# intellectual_roaddeng.net
KiCad netlist of a schematic drawn in EasyEDA Pro
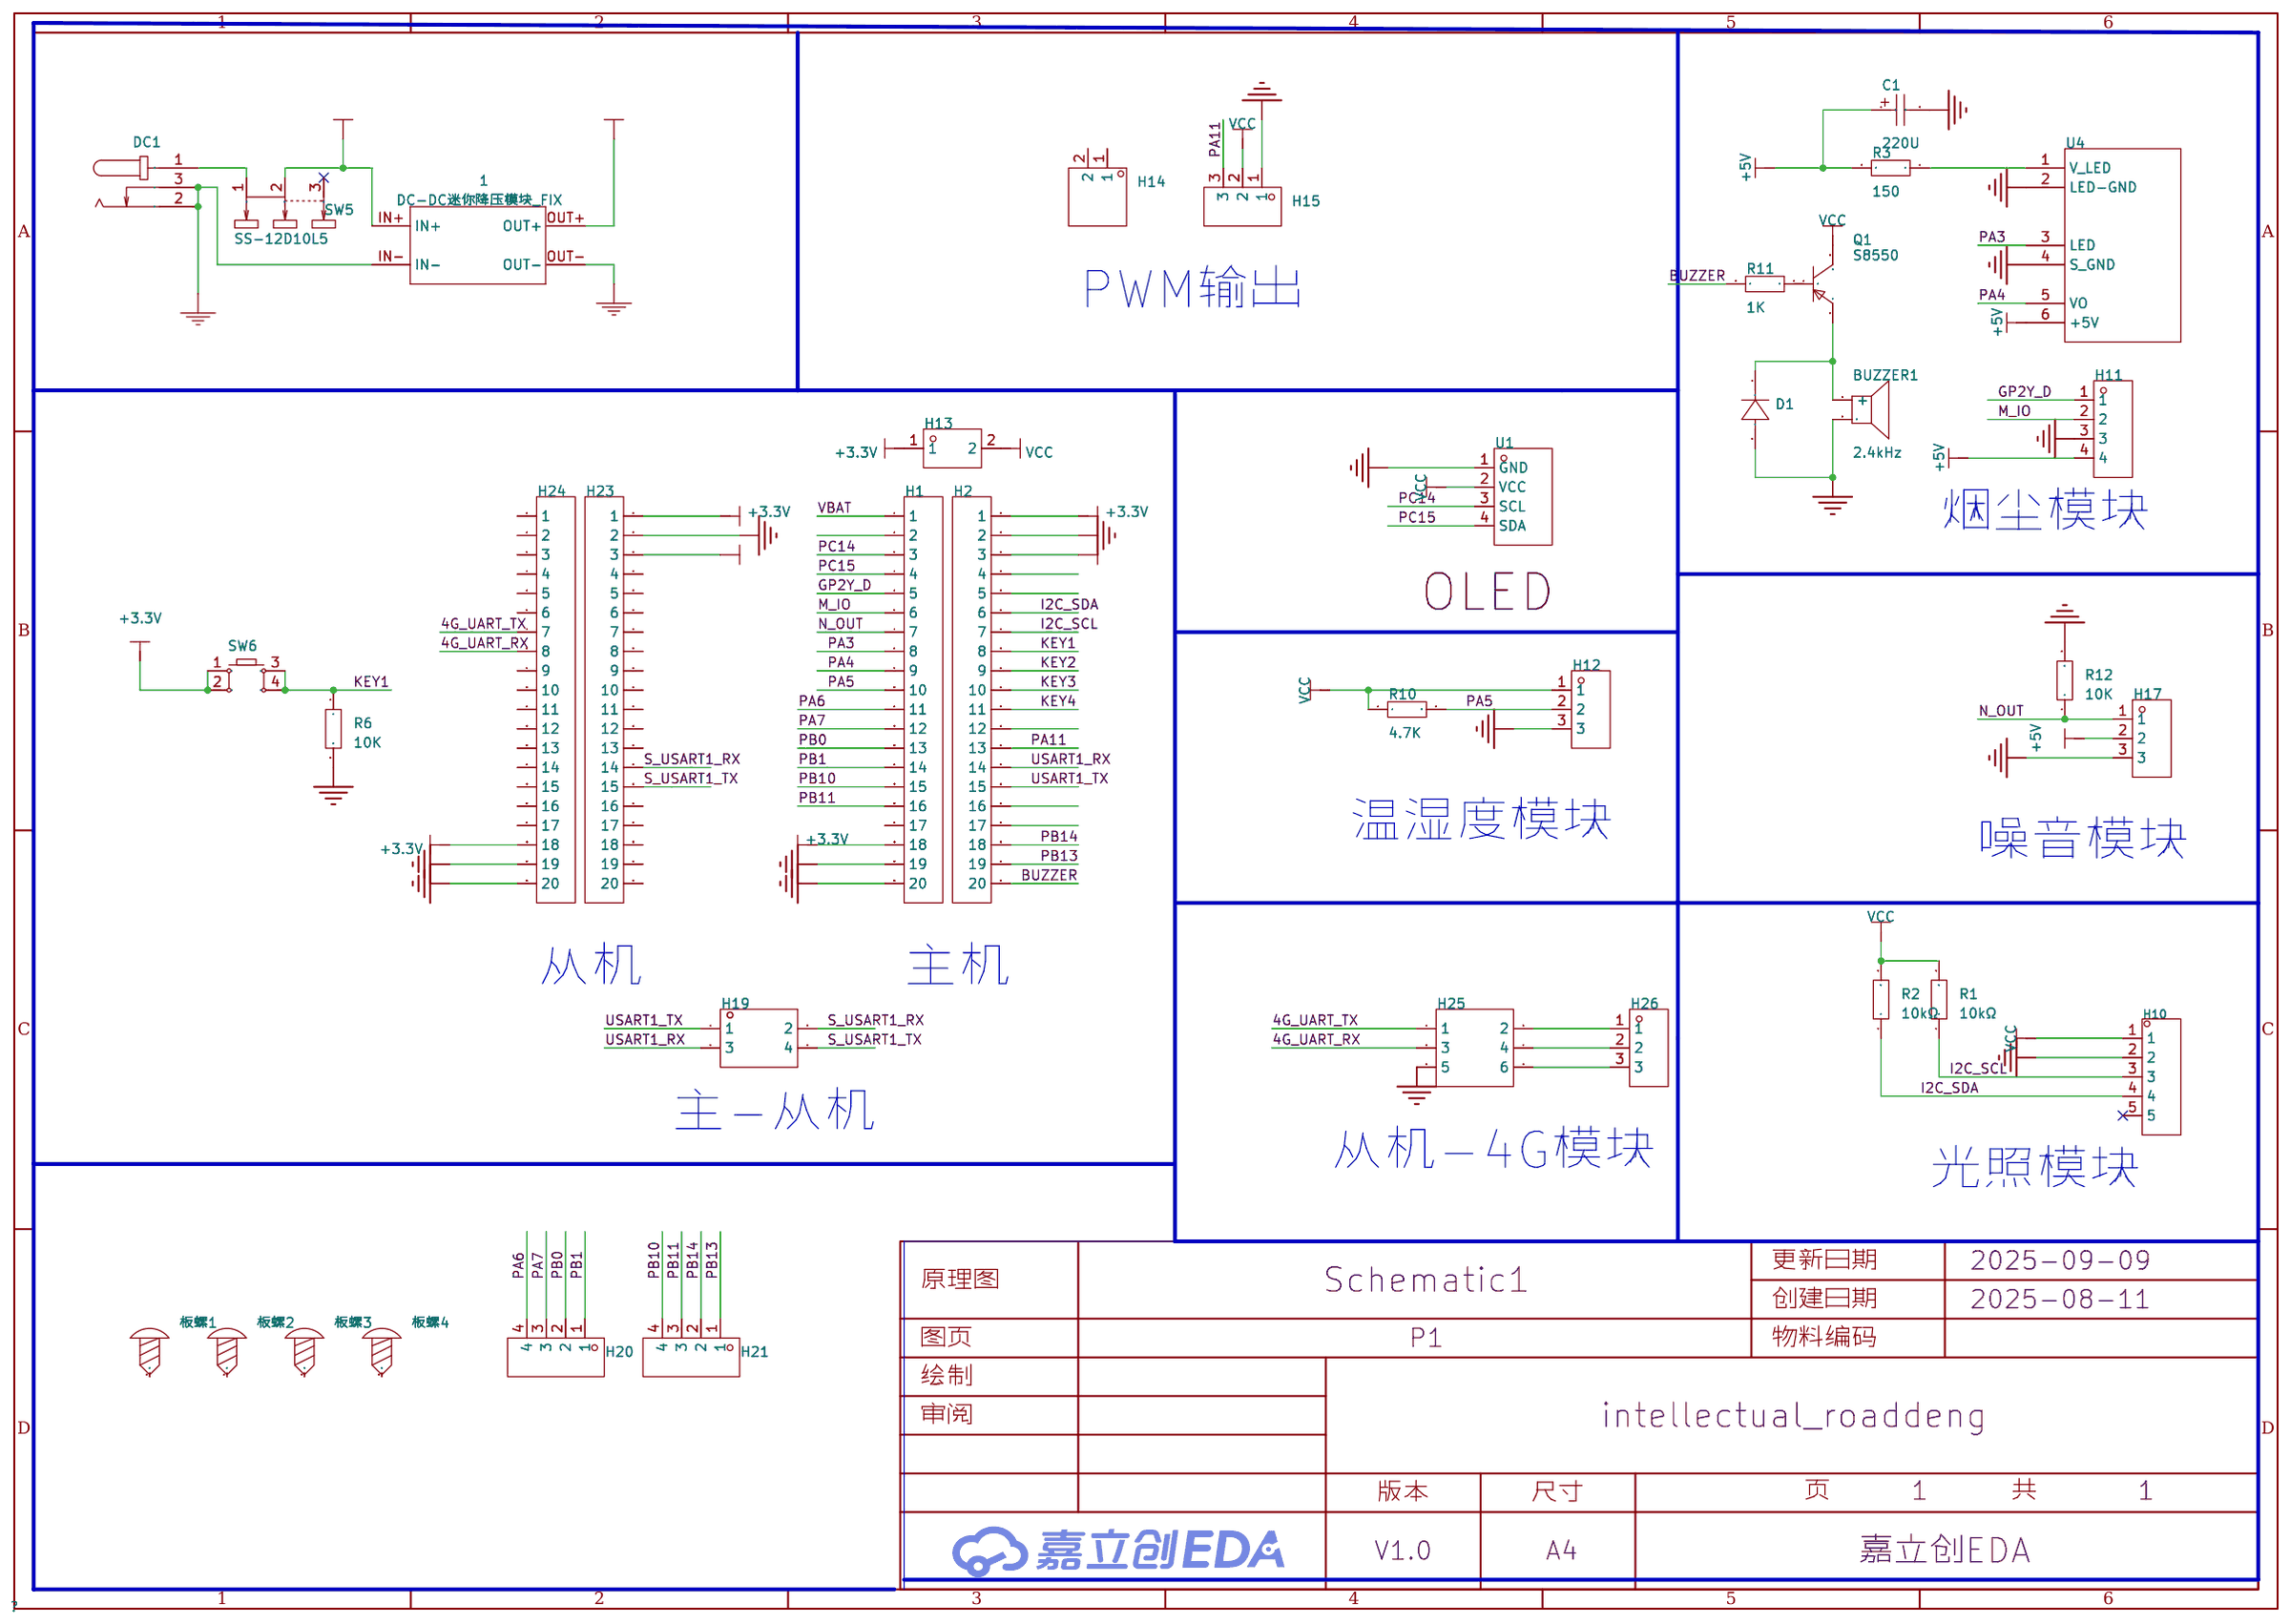
[diagram p0: schematic sheet]

(export (version "E")
  (design (tool "Eeschema 10.0.6"))
  (components
    (comp (ref "1")
      (value "DC-DC迷你降压模块_FIX")
      (footprint "easyedapro:footprint_78bd")
      (libsource (lib "easyedapro") (part "DC-DC迷你降压模块_FIX"))
    )
    (comp (ref "BUZZER1")
      (value "2.4kHz")
      (footprint "easyedapro:BUZ-TH_BD9.0-P5.00-D0.6-FD")
      (description "驱动方式:有源(内含驱动线路);构造类型:电磁式;频率:3kHz;声压(SPL):85dB;")
      (fields (field (name "Manufacturer Part") "TMB12A05") (field (name "Manufacturer") "华能"))
      (libsource (lib "easyedapro") (part "TMB12A05"))
    )
    (comp (ref "C1")
      (value "220U")
      (footprint "easyedapro:C_Ele_SMD_3x5.4mm")
      (libsource (lib "easyedapro") (part "CAP"))
    )
    (comp (ref "D1")
      (value "~")
      (footprint "easyedapro:DO_1N4007")
      (libsource (lib "easyedapro") (part "D_1N4007"))
    )
    (comp (ref "DC1")
      (value "DC005_C431533")
      (footprint "easyedapro:footprint_5569")
      (fields (field (name "Manufacturer Part") "DC005") (field (name "Manufacturer") "SHOU HAN"))
      (libsource (lib "easyedapro") (part "DC005_C431533"))
    )
    (comp (ref "H1")
      (value "HDR-F-2.54_1x20")
      (footprint "easyedapro:footprint_9e8e")
      (fields
        (field (name "Manufacturer Part") "2.54mm 1*20P Female header")
        (field (name "Manufacturer") "BOOMELE")
      )
      (libsource (lib "") (part "HDR-F-2.54_1x20_1"))
    )
    (comp (ref "H2")
      (value "HDR-F-2.54_1x20")
      (footprint "easyedapro:footprint_9e8e")
      (fields
        (field (name "Manufacturer Part") "2.54mm 1*20P Female header")
        (field (name "Manufacturer") "BOOMELE")
      )
      (libsource (lib "easyedapro") (part "HDR-F-2.54_1x20"))
    )
    (comp (ref "H10")
      (value "~")
      (footprint "easyedapro:HDR-TH_5P-P2.54-V-M")
      (libsource (lib "easyedapro") (part "MTP125-1105S1"))
    )
    (comp (ref "H11")
      (value "~")
      (footprint "easyedapro:HDR-TH_4P-P2.54-V-F")
      (libsource (lib "easyedapro") (part "2.54-1*4P母"))
    )
    (comp (ref "H12")
      (value "~")
      (footprint "easyedapro:HDR-TH_3P-P2.54-V-F")
      (libsource (lib "easyedapro") (part "PM254V-11-03-H85"))
    )
    (comp (ref "H13")
      (value "~")
      (footprint "easyedapro:HDR-TH_2P-P2.54-V-M-2")
      (libsource (lib "easyedapro") (part "HDR-M-2.54_2x1"))
    )
    (comp (ref "H14")
      (value "~")
      (footprint "easyedapro:HDR-TH_2P-P2.54-V-M-1")
      (libsource (lib "easyedapro") (part "210S-1*2P L=11.6MMGold-plated black"))
    )
    (comp (ref "H15")
      (value "~")
      (footprint "easyedapro:HDR-TH_3P-P2.54-V-M")
      (libsource (lib "easyedapro") (part "PZ254V-11-03P_C2937625"))
    )
    (comp (ref "H17")
      (value "~")
      (footprint "easyedapro:HDR-TH_3P-P2.54-V-F")
      (libsource (lib "easyedapro") (part "PM254V-11-03-H85"))
    )
    (comp (ref "H19")
      (value "~")
      (footprint "easyedapro:HDR-TH_4P-P2.54-V-F-R2-C2-S2.54")
      (libsource (lib "easyedapro") (part "HDR-F-2.54_2x2"))
    )
    (comp (ref "H20")
      (value "~")
      (footprint "easyedapro:HDR-TH_4P-P2.54-V-F")
      (libsource (lib "easyedapro") (part "2.54-1*4P母"))
    )
    (comp (ref "H21")
      (value "~")
      (footprint "easyedapro:HDR-TH_4P-P2.54-V-F")
      (libsource (lib "easyedapro") (part "2.54-1*4P母"))
    )
    (comp (ref "H23")
      (value "HDR-F-2.54_1x20")
      (footprint "easyedapro:footprint_9e8e")
      (fields
        (field (name "Manufacturer Part") "2.54mm 1*20P Female header")
        (field (name "Manufacturer") "BOOMELE")
      )
      (libsource (lib "easyedapro") (part "HDR-F-2.54_1x20"))
    )
    (comp (ref "H24")
      (value "HDR-F-2.54_1x20")
      (footprint "easyedapro:footprint_9e8e")
      (fields
        (field (name "Manufacturer Part") "2.54mm 1*20P Female header")
        (field (name "Manufacturer") "BOOMELE")
      )
      (libsource (lib "") (part "HDR-F-2.54_1x20_1"))
    )
    (comp (ref "H25")
      (value "~")
      (footprint "easyedapro:HDR-TH_6P-P2.54-V-F-R2-C3-S2.54")
      (libsource (lib "easyedapro") (part "HDR-F-2.54_2x3"))
    )
    (comp (ref "H26")
      (value "~")
      (footprint "easyedapro:HDR-TH_3P-P2.54-V-F")
      (libsource (lib "easyedapro") (part "PM254V-11-03-H85"))
    )
    (comp (ref "Q1")
      (value "S8550")
      (footprint "easyedapro:SOT-23-3_L2.9-W1.3-P1.90-LS2.4-BR")
      (description "晶体管类型:PNP;集电极电流(Ic):500mA;集射极击穿电压(Vceo):25V;耗散功率(Pd):300mW;直流电流增益(hFE):120@500mA,1.0V;")
      (fields (field (name "Manufacturer") "宏嘉诚"))
      (libsource (lib "easyedapro") (part "S8550_C20069126"))
    )
    (comp (ref "R1")
      (value "10kΩ")
      (footprint "easyedapro:Res_1/8W")
      (libsource (lib "easyedapro") (part "电阻"))
    )
    (comp (ref "R2")
      (value "10kΩ")
      (footprint "easyedapro:Res_1/8W")
      (libsource (lib "easyedapro") (part "电阻"))
    )
    (comp (ref "R3")
      (value "150")
      (footprint "easyedapro:Res_1/8W")
      (libsource (lib "easyedapro") (part "电阻"))
    )
    (comp (ref "R6")
      (value "10K")
      (footprint "easyedapro:Res_1/8W")
      (libsource (lib "easyedapro") (part "电阻"))
    )
    (comp (ref "R10")
      (value "4.7K")
      (footprint "easyedapro:Res_1/8W")
      (libsource (lib "easyedapro") (part "电阻"))
    )
    (comp (ref "R11")
      (value "1K")
      (footprint "easyedapro:Res_1/8W")
      (libsource (lib "easyedapro") (part "电阻"))
    )
    (comp (ref "R12")
      (value "10K")
      (footprint "easyedapro:Res_1/8W")
      (libsource (lib "easyedapro") (part "电阻"))
    )
    (comp (ref "SW5")
      (value "SS-12D10L5")
      (footprint "easyedapro:footprint_fc91")
      (fields (field (name "Manufacturer") "XKB Enterprise"))
      (libsource (lib "easyedapro") (part "SS-12D10L5"))
    )
    (comp (ref "SW6")
      (value "~")
      (footprint "easyedapro:Key_SMD_12x12x7.3")
      (libsource (lib "easyedapro") (part "轻触按键"))
    )
    (comp (ref "U1")
      (value "OLED")
      (footprint "easyedapro:OLED-TH_L27.8-W27.2-P2.54_C9900033791")
      (description "主控芯片:SSD1315;接口类型:I2C;尺寸(inch):0.96;像素分辨率:128x64;")
      (fields (field (name "Manufacturer") "HS(汉昇)"))
      (libsource (lib "easyedapro") (part "HS96L03W2C03"))
    )
    (comp (ref "U4") (value "~") (libsource (lib "easyedapro") (part "GP2Y1014")))
    (comp (ref "板螺1") (value "~") (footprint "easyedapro:M2螺丝") (libsource (lib "easyedapro") (part "螺丝孔")))
    (comp (ref "板螺2") (value "~") (footprint "easyedapro:M2螺丝") (libsource (lib "easyedapro") (part "螺丝孔")))
    (comp (ref "板螺3") (value "~") (footprint "easyedapro:M2螺丝") (libsource (lib "easyedapro") (part "螺丝孔")))
    (comp (ref "板螺4") (value "~") (footprint "easyedapro:M2螺丝") (libsource (lib "easyedapro") (part "螺丝孔")))
  )
  (nets
    (net (code "1") (name "+3.3V") (class "Default")
      (node (ref "H1") (pin "18") (pinfunction "18_18") (pintype "unspecified"))
      (node (ref "H13") (pin "1") (pinfunction "1_1") (pintype "input"))
      (node (ref "H2") (pin "1") (pinfunction "1_1") (pintype "unspecified"))
      (node (ref "H23") (pin "1") (pinfunction "1_1") (pintype "unspecified"))
      (node (ref "H24") (pin "18") (pinfunction "18_18") (pintype "unspecified"))
      (node (ref "SW6") (pin "1") (pinfunction "1_1") (pintype "input"))
      (node (ref "SW6") (pin "2") (pinfunction "2_2") (pintype "input"))
    )
    (net (code "2") (name "+5V") (class "Default")
      (node (ref "1") (pin "OUT+") (pinfunction "OUT+_OUT+") (pintype "bidirectional"))
      (node (ref "C1") (pin "1") (pinfunction "1_1") (pintype "input"))
      (node (ref "H11") (pin "4") (pinfunction "4_4") (pintype "unspecified"))
      (node (ref "H17") (pin "2") (pinfunction "2_2") (pintype "unspecified"))
      (node (ref "H2") (pin "3") (pinfunction "3_3") (pintype "unspecified"))
      (node (ref "H23") (pin "3") (pinfunction "3_3") (pintype "unspecified"))
      (node (ref "R3") (pin "2") (pinfunction "2_2") (pintype "input"))
      (node (ref "U4") (pin "6") (pinfunction "+5V_6") (pintype "input"))
    )
    (net (code "3") (name "/4G_UART_RX") (class "Default")
      (node (ref "H24") (pin "8") (pinfunction "8_8") (pintype "unspecified"))
      (node (ref "H25") (pin "3") (pinfunction "3_3") (pintype "input"))
    )
    (net (code "4") (name "/4G_UART_TX") (class "Default")
      (node (ref "H24") (pin "7") (pinfunction "7_7") (pintype "unspecified"))
      (node (ref "H25") (pin "1") (pinfunction "1_1") (pintype "input"))
    )
    (net (code "5") (name "/BUZZER") (class "Default")
      (node (ref "H2") (pin "20") (pinfunction "20_20") (pintype "unspecified"))
      (node (ref "R11") (pin "2") (pinfunction "2_2") (pintype "input"))
    )
    (net (code "6") (name "/GP2Y_D") (class "Default")
      (node (ref "H1") (pin "5") (pinfunction "5_5") (pintype "unspecified"))
      (node (ref "H11") (pin "1") (pinfunction "1_1") (pintype "unspecified"))
    )
    (net (code "7") (name "/I2C_SCL") (class "Default")
      (node (ref "H10") (pin "3") (pinfunction "3_3") (pintype "input"))
      (node (ref "H2") (pin "7") (pinfunction "7_7") (pintype "unspecified"))
      (node (ref "R1") (pin "1") (pinfunction "1_1") (pintype "input"))
    )
    (net (code "8") (name "/I2C_SDA") (class "Default")
      (node (ref "H10") (pin "4") (pinfunction "4_4") (pintype "input"))
      (node (ref "H2") (pin "6") (pinfunction "6_6") (pintype "unspecified"))
      (node (ref "R2") (pin "1") (pinfunction "1_1") (pintype "input"))
    )
    (net (code "9") (name "/KEY1") (class "Default")
      (node (ref "H2") (pin "8") (pinfunction "8_8") (pintype "unspecified"))
      (node (ref "R6") (pin "1") (pinfunction "1_1") (pintype "input"))
      (node (ref "SW6") (pin "3") (pinfunction "3_3") (pintype "input"))
      (node (ref "SW6") (pin "4") (pinfunction "4_4") (pintype "input"))
    )
    (net (code "10") (name "/KEY2") (class "Default")
      (node (ref "H2") (pin "9") (pinfunction "9_9") (pintype "unspecified"))
    )
    (net (code "11") (name "/KEY3") (class "Default")
      (node (ref "H2") (pin "10") (pinfunction "10_10") (pintype "unspecified"))
    )
    (net (code "12") (name "/KEY4") (class "Default")
      (node (ref "H2") (pin "11") (pinfunction "11_11") (pintype "unspecified"))
    )
    (net (code "13") (name "/M_IO") (class "Default")
      (node (ref "H1") (pin "6") (pinfunction "6_6") (pintype "unspecified"))
      (node (ref "H11") (pin "2") (pinfunction "2_2") (pintype "unspecified"))
    )
    (net (code "14") (name "/N_OUT") (class "Default")
      (node (ref "H1") (pin "7") (pinfunction "7_7") (pintype "unspecified"))
      (node (ref "H17") (pin "1") (pinfunction "1_1") (pintype "unspecified"))
      (node (ref "R12") (pin "1") (pinfunction "1_1") (pintype "input"))
    )
    (net (code "15") (name "/PA3") (class "Default")
      (node (ref "H1") (pin "8") (pinfunction "8_8") (pintype "unspecified"))
      (node (ref "U4") (pin "3") (pinfunction "LED_3") (pintype "input"))
    )
    (net (code "16") (name "/PA4") (class "Default")
      (node (ref "H1") (pin "9") (pinfunction "9_9") (pintype "unspecified"))
      (node (ref "U4") (pin "5") (pinfunction "VO_5") (pintype "input"))
    )
    (net (code "17") (name "/PA5") (class "Default")
      (node (ref "H1") (pin "10") (pinfunction "10_10") (pintype "unspecified"))
      (node (ref "H12") (pin "2") (pinfunction "2_2") (pintype "unspecified"))
      (node (ref "R10") (pin "2") (pinfunction "2_2") (pintype "input"))
    )
    (net (code "18") (name "/PA6") (class "Default")
      (node (ref "H1") (pin "11") (pinfunction "11_11") (pintype "unspecified"))
      (node (ref "H20") (pin "4") (pinfunction "4_4") (pintype "unspecified"))
    )
    (net (code "19") (name "/PA7") (class "Default")
      (node (ref "H1") (pin "12") (pinfunction "12_12") (pintype "unspecified"))
      (node (ref "H20") (pin "3") (pinfunction "3_3") (pintype "unspecified"))
    )
    (net (code "20") (name "/PA11") (class "Default")
      (node (ref "H15") (pin "3") (pinfunction "3_3") (pintype "input"))
      (node (ref "H2") (pin "13") (pinfunction "13_13") (pintype "unspecified"))
    )
    (net (code "21") (name "/PB0") (class "Default")
      (node (ref "H1") (pin "13") (pinfunction "13_13") (pintype "unspecified"))
      (node (ref "H20") (pin "2") (pinfunction "2_2") (pintype "unspecified"))
    )
    (net (code "22") (name "/PB1") (class "Default")
      (node (ref "H1") (pin "14") (pinfunction "14_14") (pintype "unspecified"))
      (node (ref "H20") (pin "1") (pinfunction "1_1") (pintype "unspecified"))
    )
    (net (code "23") (name "/PB10") (class "Default")
      (node (ref "H1") (pin "15") (pinfunction "15_15") (pintype "unspecified"))
      (node (ref "H21") (pin "4") (pinfunction "4_4") (pintype "unspecified"))
    )
    (net (code "24") (name "/PB11") (class "Default")
      (node (ref "H1") (pin "16") (pinfunction "16_16") (pintype "unspecified"))
      (node (ref "H21") (pin "3") (pinfunction "3_3") (pintype "unspecified"))
    )
    (net (code "25") (name "/PB13") (class "Default")
      (node (ref "H2") (pin "19") (pinfunction "19_19") (pintype "unspecified"))
      (node (ref "H21") (pin "1") (pinfunction "1_1") (pintype "unspecified"))
    )
    (net (code "26") (name "/PB14") (class "Default")
      (node (ref "H2") (pin "18") (pinfunction "18_18") (pintype "unspecified"))
      (node (ref "H21") (pin "2") (pinfunction "2_2") (pintype "unspecified"))
    )
    (net (code "27") (name "/PC14") (class "Default")
      (node (ref "H1") (pin "3") (pinfunction "3_3") (pintype "unspecified"))
      (node (ref "U1") (pin "3") (pinfunction "SCL_3") (pintype "unspecified"))
    )
    (net (code "28") (name "/PC15") (class "Default")
      (node (ref "H1") (pin "4") (pinfunction "4_4") (pintype "unspecified"))
      (node (ref "U1") (pin "4") (pinfunction "SDA_4") (pintype "unspecified"))
    )
    (net (code "29") (name "/S_USART1_RX") (class "Default")
      (node (ref "H19") (pin "2") (pinfunction "2_2") (pintype "input"))
      (node (ref "H23") (pin "14") (pinfunction "14_14") (pintype "unspecified"))
    )
    (net (code "30") (name "/S_USART1_TX") (class "Default")
      (node (ref "H19") (pin "4") (pinfunction "4_4") (pintype "input"))
      (node (ref "H23") (pin "15") (pinfunction "15_15") (pintype "unspecified"))
    )
    (net (code "31") (name "/USART1_RX") (class "Default")
      (node (ref "H19") (pin "3") (pinfunction "3_3") (pintype "input"))
      (node (ref "H2") (pin "14") (pinfunction "14_14") (pintype "unspecified"))
    )
    (net (code "32") (name "/USART1_TX") (class "Default")
      (node (ref "H19") (pin "1") (pinfunction "1_1") (pintype "input"))
      (node (ref "H2") (pin "15") (pinfunction "15_15") (pintype "unspecified"))
    )
    (net (code "33") (name "/VBAT") (class "Default")
      (node (ref "H1") (pin "1") (pinfunction "1_1") (pintype "unspecified"))
    )
    (net (code "34") (name "GND") (class "Default")
      (node (ref "1") (pin "IN-") (pinfunction "IN-_IN-") (pintype "bidirectional"))
      (node (ref "1") (pin "OUT-") (pinfunction "OUT-_OUT-") (pintype "bidirectional"))
      (node (ref "BUZZER1") (pin "2") (pinfunction "2_2") (pintype "unspecified"))
      (node (ref "C1") (pin "2") (pinfunction "2_2") (pintype "input"))
      (node (ref "D1") (pin "2") (pinfunction "A_2") (pintype "input"))
      (node (ref "DC1") (pin "2") (pinfunction "2_2") (pintype "unspecified"))
      (node (ref "DC1") (pin "3") (pinfunction "3_3") (pintype "unspecified"))
      (node (ref "H1") (pin "19") (pinfunction "19_19") (pintype "unspecified"))
      (node (ref "H1") (pin "20") (pinfunction "20_20") (pintype "unspecified"))
      (node (ref "H10") (pin "2") (pinfunction "2_2") (pintype "input"))
      (node (ref "H11") (pin "3") (pinfunction "3_3") (pintype "unspecified"))
      (node (ref "H12") (pin "3") (pinfunction "3_3") (pintype "unspecified"))
      (node (ref "H15") (pin "1") (pinfunction "1_1") (pintype "input"))
      (node (ref "H17") (pin "3") (pinfunction "3_3") (pintype "unspecified"))
      (node (ref "H2") (pin "2") (pinfunction "2_2") (pintype "unspecified"))
      (node (ref "H23") (pin "2") (pinfunction "2_2") (pintype "unspecified"))
      (node (ref "H24") (pin "19") (pinfunction "19_19") (pintype "unspecified"))
      (node (ref "H24") (pin "20") (pinfunction "20_20") (pintype "unspecified"))
      (node (ref "H25") (pin "5") (pinfunction "5_5") (pintype "input"))
      (node (ref "R12") (pin "2") (pinfunction "2_2") (pintype "input"))
      (node (ref "R6") (pin "2") (pinfunction "2_2") (pintype "input"))
      (node (ref "U1") (pin "1") (pinfunction "GND_1") (pintype "unspecified"))
      (node (ref "U4") (pin "2") (pinfunction "LED-GND_2") (pintype "input"))
      (node (ref "U4") (pin "4") (pinfunction "S_GND_4") (pintype "input"))
    )
    (net (code "35") (name "Net-(BUZZER1-+)") (class "Default")
      (node (ref "BUZZER1") (pin "1") (pinfunction "+_1") (pintype "unspecified"))
      (node (ref "D1") (pin "1") (pinfunction "K_1") (pintype "input"))
      (node (ref "Q1") (pin "2") (pinfunction "E_2") (pintype "input"))
    )
    (net (code "36") (name "Net-(DC1-Pad1)") (class "Default")
      (node (ref "DC1") (pin "1") (pinfunction "1_1") (pintype "unspecified"))
      (node (ref "SW5") (pin "1") (pinfunction "1_1") (pintype "unspecified"))
    )
    (net (code "37") (name "Net-(H25-Pad2)") (class "Default")
      (node (ref "H25") (pin "2") (pinfunction "2_2") (pintype "input"))
      (node (ref "H26") (pin "1") (pinfunction "1_1") (pintype "unspecified"))
    )
    (net (code "38") (name "Net-(H25-Pad4)") (class "Default")
      (node (ref "H25") (pin "4") (pinfunction "4_4") (pintype "input"))
      (node (ref "H26") (pin "2") (pinfunction "2_2") (pintype "unspecified"))
    )
    (net (code "39") (name "Net-(H25-Pad6)") (class "Default")
      (node (ref "H25") (pin "6") (pinfunction "6_6") (pintype "input"))
      (node (ref "H26") (pin "3") (pinfunction "3_3") (pintype "unspecified"))
    )
    (net (code "40") (name "Net-(Q1-B)") (class "Default")
      (node (ref "Q1") (pin "1") (pinfunction "B_1") (pintype "input"))
      (node (ref "R11") (pin "1") (pinfunction "1_1") (pintype "input"))
    )
    (net (code "41") (name "Net-(U4-V_LED)") (class "Default")
      (node (ref "R3") (pin "1") (pinfunction "1_1") (pintype "input"))
      (node (ref "U4") (pin "1") (pinfunction "V_LED_1") (pintype "input"))
    )
    (net (code "42") (name "VBAT_IN") (class "Default")
      (node (ref "1") (pin "IN+") (pinfunction "IN+_IN+") (pintype "bidirectional"))
      (node (ref "SW5") (pin "2") (pinfunction "2_2") (pintype "unspecified"))
    )
    (net (code "43") (name "VCC") (class "Default")
      (node (ref "H10") (pin "1") (pinfunction "1_1") (pintype "input"))
      (node (ref "H12") (pin "1") (pinfunction "1_1") (pintype "unspecified"))
      (node (ref "H13") (pin "2") (pinfunction "2_2") (pintype "input"))
      (node (ref "H15") (pin "2") (pinfunction "2_2") (pintype "input"))
      (node (ref "Q1") (pin "3") (pinfunction "C_3") (pintype "input"))
      (node (ref "R1") (pin "2") (pinfunction "2_2") (pintype "input"))
      (node (ref "R10") (pin "1") (pinfunction "1_1") (pintype "input"))
      (node (ref "R2") (pin "2") (pinfunction "2_2") (pintype "input"))
      (node (ref "U1") (pin "2") (pinfunction "VCC_2") (pintype "unspecified"))
    )
    (net (code "44") (name "unconnected-(H1-Pad2)") (class "Default")
      (node (ref "H1") (pin "2") (pinfunction "2_2") (pintype "unspecified"))
    )
    (net (code "45") (name "unconnected-(H1-Pad17)") (class "Default")
      (node (ref "H1") (pin "17") (pinfunction "17_17") (pintype "unspecified"))
    )
    (net (code "46") (name "unconnected-(H2-Pad4)") (class "Default")
      (node (ref "H2") (pin "4") (pinfunction "4_4") (pintype "unspecified"))
    )
    (net (code "47") (name "unconnected-(H2-Pad5)") (class "Default")
      (node (ref "H2") (pin "5") (pinfunction "5_5") (pintype "unspecified"))
    )
    (net (code "48") (name "unconnected-(H2-Pad12)") (class "Default")
      (node (ref "H2") (pin "12") (pinfunction "12_12") (pintype "unspecified"))
    )
    (net (code "49") (name "unconnected-(H2-Pad16)") (class "Default")
      (node (ref "H2") (pin "16") (pinfunction "16_16") (pintype "unspecified"))
    )
    (net (code "50") (name "unconnected-(H2-Pad17)") (class "Default")
      (node (ref "H2") (pin "17") (pinfunction "17_17") (pintype "unspecified"))
    )
    (net (code "51") (name "unconnected-(H10-Pad5)") (class "Default")
      (node (ref "H10") (pin "5") (pinfunction "5_5") (pintype "input+no_connect"))
    )
    (net (code "52") (name "unconnected-(H14-Pad1)") (class "Default")
      (node (ref "H14") (pin "1") (pinfunction "1_1") (pintype "unspecified"))
    )
    (net (code "53") (name "unconnected-(H14-Pad2)") (class "Default")
      (node (ref "H14") (pin "2") (pinfunction "2_2") (pintype "unspecified"))
    )
    (net (code "54") (name "unconnected-(H23-Pad4)") (class "Default")
      (node (ref "H23") (pin "4") (pinfunction "4_4") (pintype "unspecified"))
    )
    (net (code "55") (name "unconnected-(H23-Pad5)") (class "Default")
      (node (ref "H23") (pin "5") (pinfunction "5_5") (pintype "unspecified"))
    )
    (net (code "56") (name "unconnected-(H23-Pad6)") (class "Default")
      (node (ref "H23") (pin "6") (pinfunction "6_6") (pintype "unspecified"))
    )
    (net (code "57") (name "unconnected-(H23-Pad7)") (class "Default")
      (node (ref "H23") (pin "7") (pinfunction "7_7") (pintype "unspecified"))
    )
    (net (code "58") (name "unconnected-(H23-Pad8)") (class "Default")
      (node (ref "H23") (pin "8") (pinfunction "8_8") (pintype "unspecified"))
    )
    (net (code "59") (name "unconnected-(H23-Pad9)") (class "Default")
      (node (ref "H23") (pin "9") (pinfunction "9_9") (pintype "unspecified"))
    )
    (net (code "60") (name "unconnected-(H23-Pad10)") (class "Default")
      (node (ref "H23") (pin "10") (pinfunction "10_10") (pintype "unspecified"))
    )
    (net (code "61") (name "unconnected-(H23-Pad11)") (class "Default")
      (node (ref "H23") (pin "11") (pinfunction "11_11") (pintype "unspecified"))
    )
    (net (code "62") (name "unconnected-(H23-Pad12)") (class "Default")
      (node (ref "H23") (pin "12") (pinfunction "12_12") (pintype "unspecified"))
    )
    (net (code "63") (name "unconnected-(H23-Pad13)") (class "Default")
      (node (ref "H23") (pin "13") (pinfunction "13_13") (pintype "unspecified"))
    )
    (net (code "64") (name "unconnected-(H23-Pad16)") (class "Default")
      (node (ref "H23") (pin "16") (pinfunction "16_16") (pintype "unspecified"))
    )
    (net (code "65") (name "unconnected-(H23-Pad17)") (class "Default")
      (node (ref "H23") (pin "17") (pinfunction "17_17") (pintype "unspecified"))
    )
    (net (code "66") (name "unconnected-(H23-Pad18)") (class "Default")
      (node (ref "H23") (pin "18") (pinfunction "18_18") (pintype "unspecified"))
    )
    (net (code "67") (name "unconnected-(H23-Pad19)") (class "Default")
      (node (ref "H23") (pin "19") (pinfunction "19_19") (pintype "unspecified"))
    )
    (net (code "68") (name "unconnected-(H23-Pad20)") (class "Default")
      (node (ref "H23") (pin "20") (pinfunction "20_20") (pintype "unspecified"))
    )
    (net (code "69") (name "unconnected-(H24-Pad1)") (class "Default")
      (node (ref "H24") (pin "1") (pinfunction "1_1") (pintype "unspecified"))
    )
    (net (code "70") (name "unconnected-(H24-Pad2)") (class "Default")
      (node (ref "H24") (pin "2") (pinfunction "2_2") (pintype "unspecified"))
    )
    (net (code "71") (name "unconnected-(H24-Pad3)") (class "Default")
      (node (ref "H24") (pin "3") (pinfunction "3_3") (pintype "unspecified"))
    )
    (net (code "72") (name "unconnected-(H24-Pad4)") (class "Default")
      (node (ref "H24") (pin "4") (pinfunction "4_4") (pintype "unspecified"))
    )
    (net (code "73") (name "unconnected-(H24-Pad5)") (class "Default")
      (node (ref "H24") (pin "5") (pinfunction "5_5") (pintype "unspecified"))
    )
    (net (code "74") (name "unconnected-(H24-Pad6)") (class "Default")
      (node (ref "H24") (pin "6") (pinfunction "6_6") (pintype "unspecified"))
    )
    (net (code "75") (name "unconnected-(H24-Pad9)") (class "Default")
      (node (ref "H24") (pin "9") (pinfunction "9_9") (pintype "unspecified"))
    )
    (net (code "76") (name "unconnected-(H24-Pad10)") (class "Default")
      (node (ref "H24") (pin "10") (pinfunction "10_10") (pintype "unspecified"))
    )
    (net (code "77") (name "unconnected-(H24-Pad11)") (class "Default")
      (node (ref "H24") (pin "11") (pinfunction "11_11") (pintype "unspecified"))
    )
    (net (code "78") (name "unconnected-(H24-Pad12)") (class "Default")
      (node (ref "H24") (pin "12") (pinfunction "12_12") (pintype "unspecified"))
    )
    (net (code "79") (name "unconnected-(H24-Pad13)") (class "Default")
      (node (ref "H24") (pin "13") (pinfunction "13_13") (pintype "unspecified"))
    )
    (net (code "80") (name "unconnected-(H24-Pad14)") (class "Default")
      (node (ref "H24") (pin "14") (pinfunction "14_14") (pintype "unspecified"))
    )
    (net (code "81") (name "unconnected-(H24-Pad15)") (class "Default")
      (node (ref "H24") (pin "15") (pinfunction "15_15") (pintype "unspecified"))
    )
    (net (code "82") (name "unconnected-(H24-Pad16)") (class "Default")
      (node (ref "H24") (pin "16") (pinfunction "16_16") (pintype "unspecified"))
    )
    (net (code "83") (name "unconnected-(H24-Pad17)") (class "Default")
      (node (ref "H24") (pin "17") (pinfunction "17_17") (pintype "unspecified"))
    )
    (net (code "84") (name "unconnected-(SW5-Pad3)") (class "Default")
      (node (ref "SW5") (pin "3") (pinfunction "3_3") (pintype "unspecified+no_connect"))
    )
    (net (code "85") (name "unconnected-(板螺1-Pad1)") (class "Default")
      (node (ref "板螺1") (pin "1") (pinfunction "1_1") (pintype "input"))
    )
    (net (code "86") (name "unconnected-(板螺2-Pad1)") (class "Default")
      (node (ref "板螺2") (pin "1") (pinfunction "1_1") (pintype "input"))
    )
    (net (code "87") (name "unconnected-(板螺3-Pad1)") (class "Default")
      (node (ref "板螺3") (pin "1") (pinfunction "1_1") (pintype "input"))
    )
    (net (code "88") (name "unconnected-(板螺4-Pad1)") (class "Default")
      (node (ref "板螺4") (pin "1") (pinfunction "1_1") (pintype "input"))
    )
  )
)
